# Internal_A.net
KiCad netlist of a schematic drawn in EAGLE
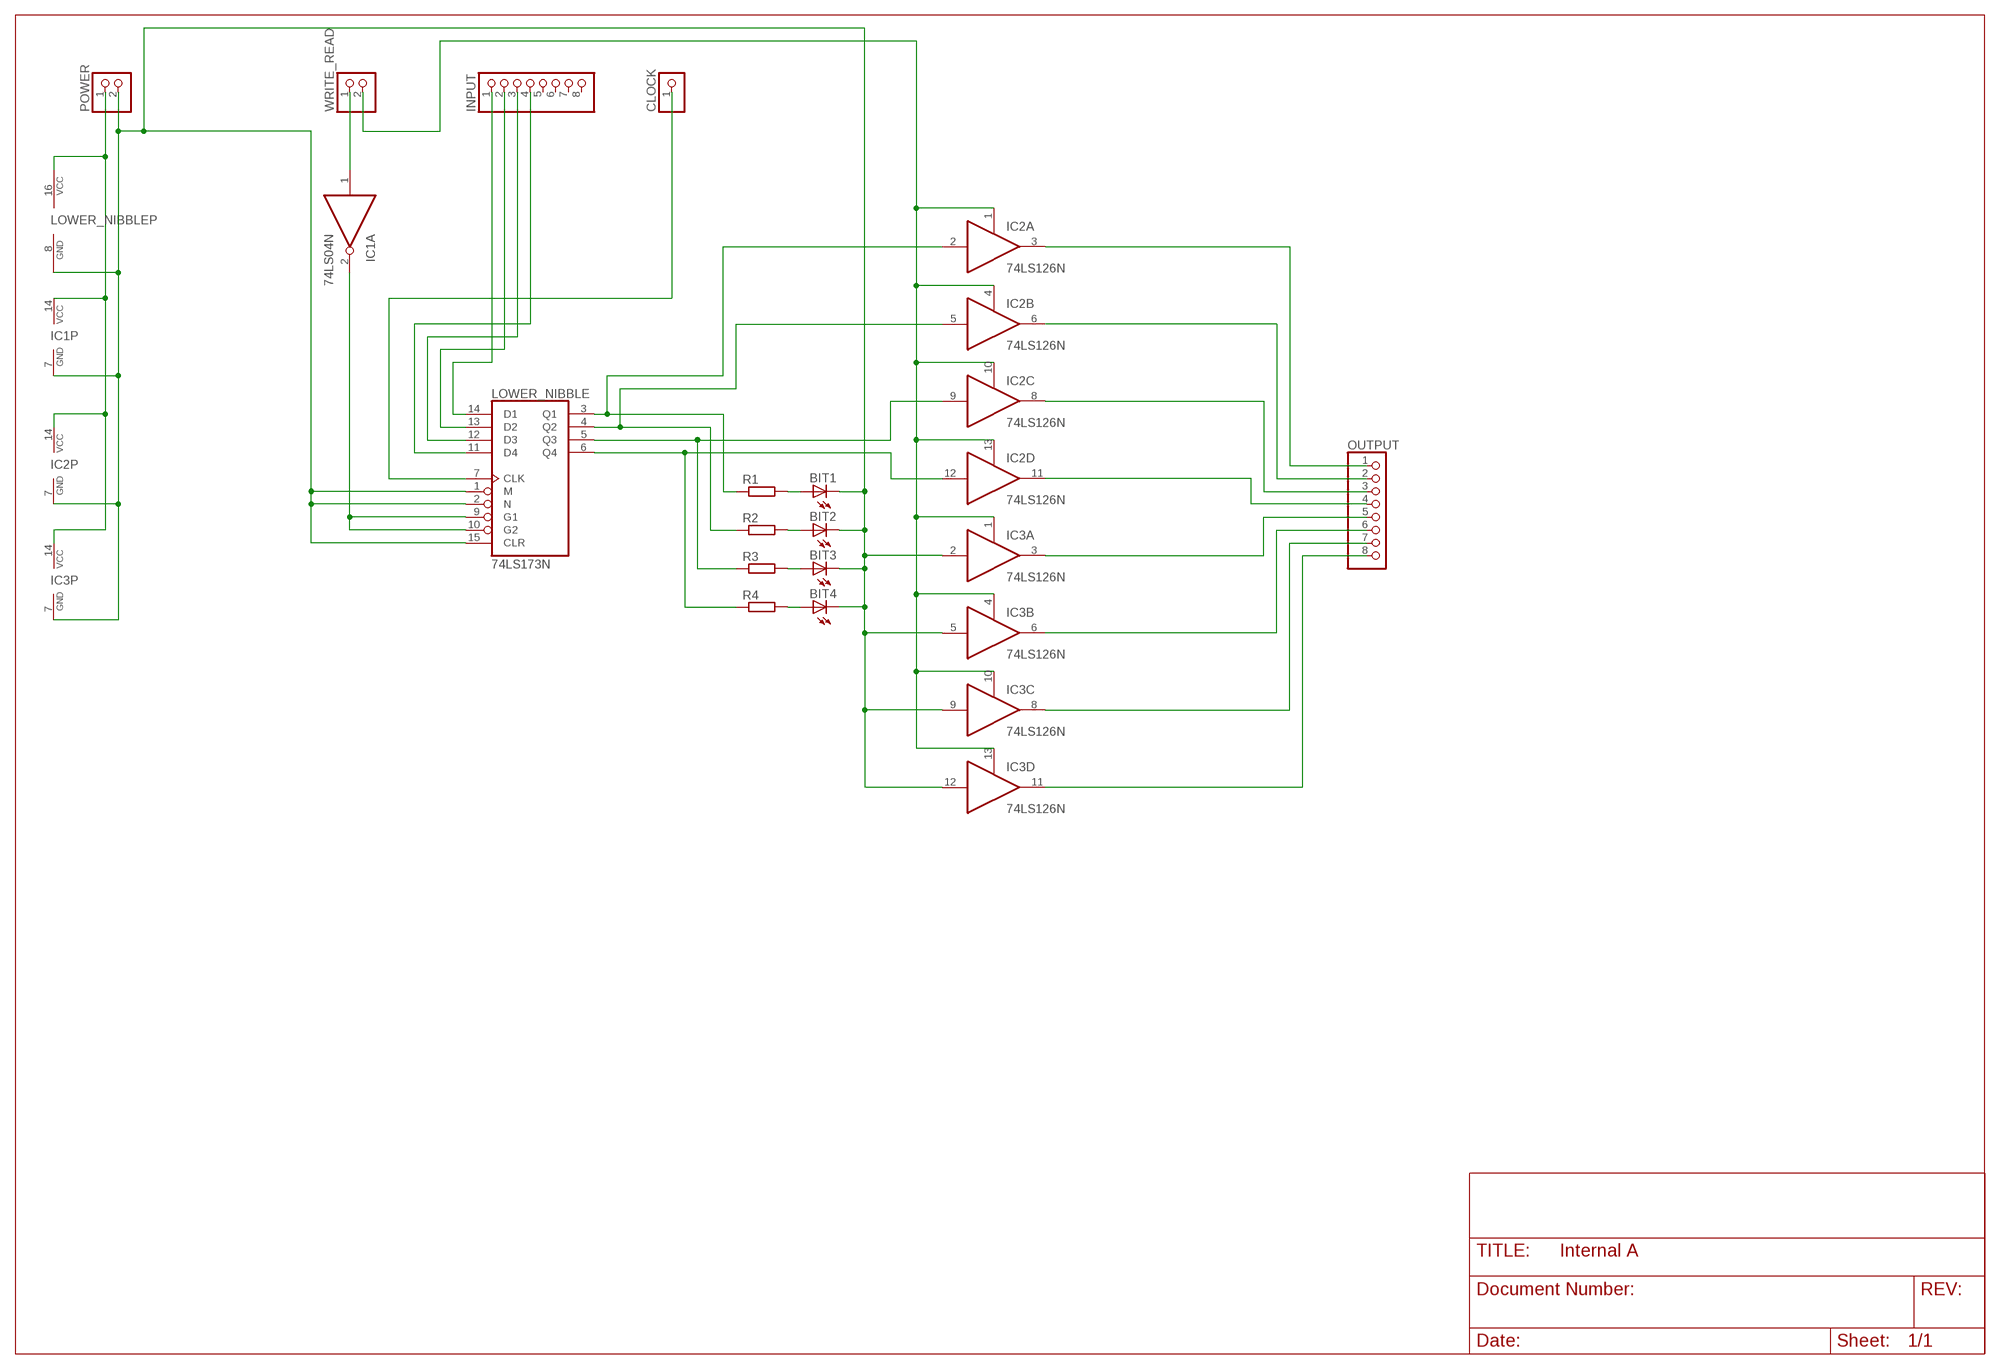
[diagram p0: schematic, sheet 1]

(export (version "E")
  (design (tool "Eeschema 10.0.6"))
  (components
    (comp (ref "BIT1")
      (value "LED3MM")
      (footprint "eagle-import:LED3MM")
      (libsource (lib "eagle-import") (part "LED3MM"))
    )
    (comp (ref "BIT2")
      (value "LED3MM")
      (footprint "eagle-import:LED3MM")
      (libsource (lib "eagle-import") (part "LED3MM"))
    )
    (comp (ref "BIT3")
      (value "LED3MM")
      (footprint "eagle-import:LED3MM")
      (libsource (lib "eagle-import") (part "LED3MM"))
    )
    (comp (ref "BIT4")
      (value "LED3MM")
      (footprint "eagle-import:LED3MM")
      (libsource (lib "eagle-import") (part "LED3MM"))
    )
    (comp (ref "CLOCK")
      (value "PINHD-1X1")
      (footprint "eagle-import:1X01")
      (libsource (lib "eagle-import") (part "PINHD-1X1"))
    )
    (comp (ref "IC1")
      (value "74LS04N")
      (footprint "eagle-import:DIL14")
      (libsource (lib "eagle-import") (part "7404NLS"))
    )
    (comp (ref "IC2")
      (value "74LS126N")
      (footprint "eagle-import:DIL14")
      (libsource (lib "eagle-import") (part "74126NLS"))
    )
    (comp (ref "IC3")
      (value "74LS126N")
      (footprint "eagle-import:DIL14")
      (libsource (lib "eagle-import") (part "74126NLS"))
    )
    (comp (ref "INPUT")
      (value "PINHD-1X8")
      (footprint "eagle-import:1X08")
      (libsource (lib "eagle-import") (part "PINHD-1X8"))
    )
    (comp (ref "LOWER_NIBBLE")
      (value "74LS173N")
      (footprint "eagle-import:DIL16")
      (libsource (lib "eagle-import") (part "74173NLS"))
    )
    (comp (ref "OUTPUT")
      (value "PINHD-1X8")
      (footprint "eagle-import:1X08")
      (libsource (lib "eagle-import") (part "PINHD-1X8"))
    )
    (comp (ref "POWER")
      (value "PINHD-1X2")
      (footprint "eagle-import:1X02")
      (libsource (lib "eagle-import") (part "PINHD-1X2"))
    )
    (comp (ref "R1")
      (value "R-EU_0207/10")
      (footprint "eagle-import:0207_10")
      (libsource (lib "eagle-import") (part "R-EU_0207/10"))
    )
    (comp (ref "R2")
      (value "R-EU_0207/10")
      (footprint "eagle-import:0207_10")
      (libsource (lib "eagle-import") (part "R-EU_0207/10"))
    )
    (comp (ref "R3")
      (value "R-EU_0207/10")
      (footprint "eagle-import:0207_10")
      (libsource (lib "eagle-import") (part "R-EU_0207/10"))
    )
    (comp (ref "R4")
      (value "R-EU_0207/10")
      (footprint "eagle-import:0207_10")
      (libsource (lib "eagle-import") (part "R-EU_0207/10"))
    )
    (comp (ref "WRITE_READ")
      (value "PINHD-1X2")
      (footprint "eagle-import:1X02")
      (libsource (lib "eagle-import") (part "PINHD-1X2"))
    )
  )
  (nets
    (net (code "1") (name "Net-(BIT1-C)") (class "Default")
      (node (ref "BIT1") (pin "K") (pinfunction "C_K") (pintype "passive"))
      (node (ref "BIT2") (pin "K") (pinfunction "C_K") (pintype "passive"))
      (node (ref "BIT3") (pin "K") (pinfunction "C_K") (pintype "passive"))
      (node (ref "BIT4") (pin "K") (pinfunction "C_K") (pintype "passive"))
      (node (ref "IC1") (pin "7") (pinfunction "GND_7") (pintype "power_in"))
      (node (ref "IC2") (pin "7") (pinfunction "GND_7") (pintype "power_in"))
      (node (ref "IC3") (pin "12") (pinfunction "I_12") (pintype "input"))
      (node (ref "IC3") (pin "2") (pinfunction "I_2") (pintype "input"))
      (node (ref "IC3") (pin "5") (pinfunction "I_5") (pintype "input"))
      (node (ref "IC3") (pin "7") (pinfunction "GND_7") (pintype "power_in"))
      (node (ref "IC3") (pin "9") (pinfunction "I_9") (pintype "input"))
      (node (ref "LOWER_NIBBLE") (pin "1") (pinfunction "M_1") (pintype "input"))
      (node (ref "LOWER_NIBBLE") (pin "15") (pinfunction "CLR_15") (pintype "input"))
      (node (ref "LOWER_NIBBLE") (pin "2") (pinfunction "N_2") (pintype "input"))
      (node (ref "LOWER_NIBBLE") (pin "8") (pinfunction "GND_8") (pintype "power_in"))
      (node (ref "POWER") (pin "2") (pinfunction "2_2") (pintype "passive"))
    )
    (net (code "2") (name "Net-(BIT1-PadA)") (class "Default")
      (node (ref "BIT1") (pin "A") (pinfunction "A_A") (pintype "passive"))
      (node (ref "R1") (pin "2") (pinfunction "2_2") (pintype "passive"))
    )
    (net (code "3") (name "Net-(BIT2-PadA)") (class "Default")
      (node (ref "BIT2") (pin "A") (pinfunction "A_A") (pintype "passive"))
      (node (ref "R2") (pin "2") (pinfunction "2_2") (pintype "passive"))
    )
    (net (code "4") (name "Net-(BIT3-PadA)") (class "Default")
      (node (ref "BIT3") (pin "A") (pinfunction "A_A") (pintype "passive"))
      (node (ref "R3") (pin "2") (pinfunction "2_2") (pintype "passive"))
    )
    (net (code "5") (name "Net-(BIT4-PadA)") (class "Default")
      (node (ref "BIT4") (pin "A") (pinfunction "A_A") (pintype "passive"))
      (node (ref "R4") (pin "2") (pinfunction "2_2") (pintype "passive"))
    )
    (net (code "6") (name "Net-(IC1A-I)") (class "Default")
      (node (ref "IC1") (pin "1") (pinfunction "I_1") (pintype "input"))
      (node (ref "WRITE_READ") (pin "1") (pinfunction "1_1") (pintype "passive"))
    )
    (net (code "7") (name "Net-(IC1A-O)") (class "Default")
      (node (ref "IC1") (pin "2") (pinfunction "O_2") (pintype "output"))
      (node (ref "LOWER_NIBBLE") (pin "10") (pinfunction "G2_10") (pintype "input"))
      (node (ref "LOWER_NIBBLE") (pin "9") (pinfunction "G1_9") (pintype "input"))
    )
    (net (code "8") (name "Net-(IC1G-VCC)") (class "Default")
      (node (ref "IC1") (pin "14") (pinfunction "VCC_14") (pintype "power_in"))
      (node (ref "IC2") (pin "14") (pinfunction "VCC_14") (pintype "power_in"))
      (node (ref "IC3") (pin "14") (pinfunction "VCC_14") (pintype "power_in"))
      (node (ref "LOWER_NIBBLE") (pin "16") (pinfunction "VCC_16") (pintype "power_in"))
      (node (ref "POWER") (pin "1") (pinfunction "1_1") (pintype "passive"))
    )
    (net (code "9") (name "Net-(IC2A-I)") (class "Default")
      (node (ref "IC2") (pin "2") (pinfunction "I_2") (pintype "input"))
      (node (ref "LOWER_NIBBLE") (pin "3") (pinfunction "Q1_3") (pintype "tri_state"))
      (node (ref "R1") (pin "1") (pinfunction "1_1") (pintype "passive"))
    )
    (net (code "10") (name "Net-(IC2A-O)") (class "Default")
      (node (ref "IC2") (pin "3") (pinfunction "O_3") (pintype "output"))
      (node (ref "OUTPUT") (pin "1") (pinfunction "1_1") (pintype "passive"))
    )
    (net (code "11") (name "Net-(IC2A-OE)") (class "Default")
      (node (ref "IC2") (pin "1") (pinfunction "OE_1") (pintype "input"))
      (node (ref "IC2") (pin "10") (pinfunction "OE_10") (pintype "input"))
      (node (ref "IC2") (pin "13") (pinfunction "OE_13") (pintype "input"))
      (node (ref "IC2") (pin "4") (pinfunction "OE_4") (pintype "input"))
      (node (ref "IC3") (pin "1") (pinfunction "OE_1") (pintype "input"))
      (node (ref "IC3") (pin "10") (pinfunction "OE_10") (pintype "input"))
      (node (ref "IC3") (pin "13") (pinfunction "OE_13") (pintype "input"))
      (node (ref "IC3") (pin "4") (pinfunction "OE_4") (pintype "input"))
      (node (ref "WRITE_READ") (pin "2") (pinfunction "2_2") (pintype "passive"))
    )
    (net (code "12") (name "Net-(IC2B-I)") (class "Default")
      (node (ref "IC2") (pin "5") (pinfunction "I_5") (pintype "input"))
      (node (ref "LOWER_NIBBLE") (pin "4") (pinfunction "Q2_4") (pintype "tri_state"))
      (node (ref "R2") (pin "1") (pinfunction "1_1") (pintype "passive"))
    )
    (net (code "13") (name "Net-(IC2B-O)") (class "Default")
      (node (ref "IC2") (pin "6") (pinfunction "O_6") (pintype "output"))
      (node (ref "OUTPUT") (pin "2") (pinfunction "2_2") (pintype "passive"))
    )
    (net (code "14") (name "Net-(IC2C-I)") (class "Default")
      (node (ref "IC2") (pin "9") (pinfunction "I_9") (pintype "input"))
      (node (ref "LOWER_NIBBLE") (pin "5") (pinfunction "Q3_5") (pintype "tri_state"))
      (node (ref "R3") (pin "1") (pinfunction "1_1") (pintype "passive"))
    )
    (net (code "15") (name "Net-(IC2C-O)") (class "Default")
      (node (ref "IC2") (pin "8") (pinfunction "O_8") (pintype "output"))
      (node (ref "OUTPUT") (pin "3") (pinfunction "3_3") (pintype "passive"))
    )
    (net (code "16") (name "Net-(IC2D-I)") (class "Default")
      (node (ref "IC2") (pin "12") (pinfunction "I_12") (pintype "input"))
      (node (ref "LOWER_NIBBLE") (pin "6") (pinfunction "Q4_6") (pintype "tri_state"))
      (node (ref "R4") (pin "1") (pinfunction "1_1") (pintype "passive"))
    )
    (net (code "17") (name "Net-(IC2D-O)") (class "Default")
      (node (ref "IC2") (pin "11") (pinfunction "O_11") (pintype "output"))
      (node (ref "OUTPUT") (pin "4") (pinfunction "4_4") (pintype "passive"))
    )
    (net (code "18") (name "Net-(IC3A-O)") (class "Default")
      (node (ref "IC3") (pin "3") (pinfunction "O_3") (pintype "output"))
      (node (ref "OUTPUT") (pin "5") (pinfunction "5_5") (pintype "passive"))
    )
    (net (code "19") (name "Net-(IC3B-O)") (class "Default")
      (node (ref "IC3") (pin "6") (pinfunction "O_6") (pintype "output"))
      (node (ref "OUTPUT") (pin "6") (pinfunction "6_6") (pintype "passive"))
    )
    (net (code "20") (name "Net-(IC3C-O)") (class "Default")
      (node (ref "IC3") (pin "8") (pinfunction "O_8") (pintype "output"))
      (node (ref "OUTPUT") (pin "7") (pinfunction "7_7") (pintype "passive"))
    )
    (net (code "21") (name "Net-(IC3D-O)") (class "Default")
      (node (ref "IC3") (pin "11") (pinfunction "O_11") (pintype "output"))
      (node (ref "OUTPUT") (pin "8") (pinfunction "8_8") (pintype "passive"))
    )
    (net (code "22") (name "Net-(LOWER_NIBBLEA-CLK)") (class "Default")
      (node (ref "CLOCK") (pin "1") (pinfunction "1_1") (pintype "passive"))
      (node (ref "LOWER_NIBBLE") (pin "7") (pinfunction "CLK_7") (pintype "input"))
    )
    (net (code "23") (name "Net-(LOWER_NIBBLEA-D1)") (class "Default")
      (node (ref "INPUT") (pin "1") (pinfunction "1_1") (pintype "passive"))
      (node (ref "LOWER_NIBBLE") (pin "14") (pinfunction "D1_14") (pintype "input"))
    )
    (net (code "24") (name "Net-(LOWER_NIBBLEA-D2)") (class "Default")
      (node (ref "INPUT") (pin "2") (pinfunction "2_2") (pintype "passive"))
      (node (ref "LOWER_NIBBLE") (pin "13") (pinfunction "D2_13") (pintype "input"))
    )
    (net (code "25") (name "Net-(LOWER_NIBBLEA-D3)") (class "Default")
      (node (ref "INPUT") (pin "3") (pinfunction "3_3") (pintype "passive"))
      (node (ref "LOWER_NIBBLE") (pin "12") (pinfunction "D3_12") (pintype "input"))
    )
    (net (code "26") (name "Net-(LOWER_NIBBLEA-D4)") (class "Default")
      (node (ref "INPUT") (pin "4") (pinfunction "4_4") (pintype "passive"))
      (node (ref "LOWER_NIBBLE") (pin "11") (pinfunction "D4_11") (pintype "input"))
    )
    (net (code "27") (name "unconnected-(INPUT-Pad5)") (class "Default")
      (node (ref "INPUT") (pin "5") (pinfunction "5_5") (pintype "passive"))
    )
    (net (code "28") (name "unconnected-(INPUT-Pad6)") (class "Default")
      (node (ref "INPUT") (pin "6") (pinfunction "6_6") (pintype "passive"))
    )
    (net (code "29") (name "unconnected-(INPUT-Pad7)") (class "Default")
      (node (ref "INPUT") (pin "7") (pinfunction "7_7") (pintype "passive"))
    )
    (net (code "30") (name "unconnected-(INPUT-Pad8)") (class "Default")
      (node (ref "INPUT") (pin "8") (pinfunction "8_8") (pintype "passive"))
    )
  )
)
